# D1_Breakout_-_LCD_TH_Dupont.net
KiCad netlist of a schematic drawn in EAGLE
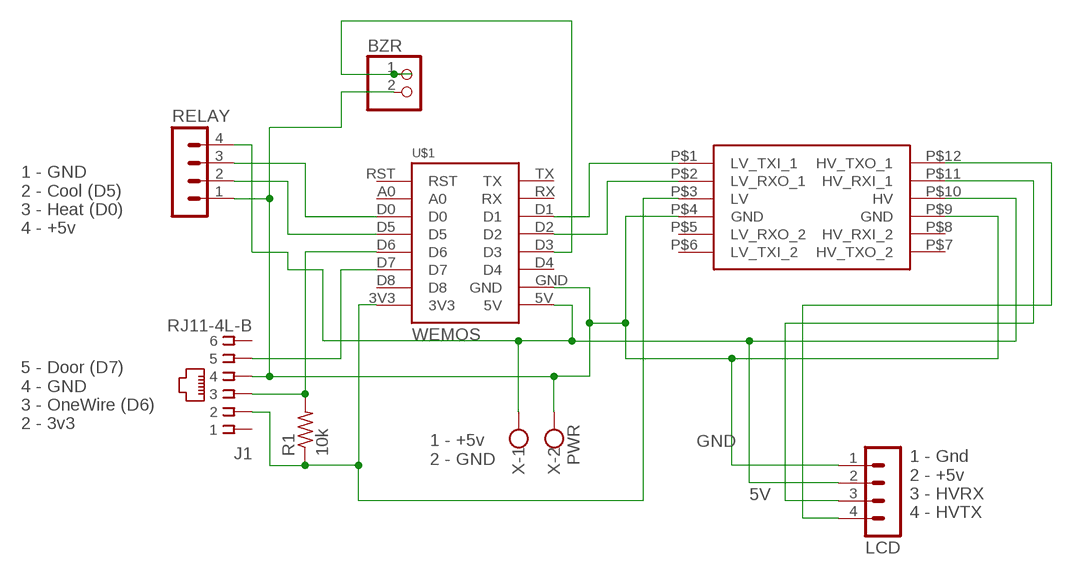
[diagram p0: schematic, sheet 1]

(export (version "E")
  (design (tool "Eeschema 10.0.6"))
  (components
    (comp (ref "BZR")
      (value "PINHD-1X2")
      (footprint "eagle-import:1X02")
      (libsource (lib "eagle-import") (part "PINHD-1X2"))
    )
    (comp (ref "J1")
      (value "RJ11-4L-B")
      (footprint "eagle-import:RJ11-NO_SHIELD")
      (fields (field (name "MF") "TYCO ELECTRONICS"))
      (libsource (lib "eagle-import") (part "RJ11-4L-B"))
    )
    (comp (ref "LCD")
      (value "MA04-1")
      (footprint "eagle-import:MA04-1")
      (libsource (lib "eagle-import") (part "MA04-1"))
    )
    (comp (ref "R1")
      (value "10k")
      (footprint "eagle-import:0207_5V")
      (libsource (lib "eagle-import") (part "R-US_0207/5V"))
    )
    (comp (ref "RELAY")
      (value "MA04-1")
      (footprint "eagle-import:MA04-1")
      (libsource (lib "eagle-import") (part "MA04-1"))
    )
    (comp (ref "U$1")
      (value "WEMOS")
      (footprint "eagle-import:WEMOS")
      (libsource (lib "eagle-import") (part "WEMOS"))
    )
    (comp (ref "U$3")
      (value "LOGIC_LEVEL_CONVERTER")
      (footprint "eagle-import:LOGIC_LEVEL_CONVERTER")
      (libsource (lib "eagle-import") (part "LOGIC_LEVEL_CONVERTER"))
    )
    (comp (ref "X")
      (value "PWR")
      (footprint "eagle-import:W237-102")
      (fields (field (name "MPN") "237-102"))
      (libsource (lib "eagle-import") (part "W237-102"))
    )
  )
  (nets
    (net (code "1") (name "/5V") (class "Default")
      (node (ref "LCD") (pin "2") (pinfunction "2_2") (pintype "passive"))
      (node (ref "RELAY") (pin "4") (pinfunction "4_4") (pintype "passive"))
      (node (ref "U$1") (pin "5V") (pinfunction "5V_5V") (pintype "bidirectional"))
      (node (ref "U$3") (pin "P$10") (pinfunction "HV_P$10") (pintype "bidirectional"))
      (node (ref "X") (pin "1") (pinfunction "KL_1") (pintype "passive"))
    )
    (net (code "2") (name "/GND") (class "Default")
      (node (ref "BZR") (pin "2") (pinfunction "2_2") (pintype "passive"))
      (node (ref "J1") (pin "4") (pinfunction "4_4") (pintype "passive"))
      (node (ref "LCD") (pin "1") (pinfunction "1_1") (pintype "passive"))
      (node (ref "RELAY") (pin "1") (pinfunction "1_1") (pintype "passive"))
      (node (ref "U$1") (pin "GND") (pinfunction "GND_GND") (pintype "bidirectional"))
      (node (ref "U$3") (pin "P$4") (pinfunction "GND_P$4") (pintype "bidirectional"))
      (node (ref "U$3") (pin "P$9") (pinfunction "GND_P$9") (pintype "bidirectional"))
      (node (ref "X") (pin "2") (pinfunction "KL_2") (pintype "passive"))
    )
    (net (code "3") (name "Net-(BZR-Pad1)") (class "Default")
      (node (ref "BZR") (pin "1") (pinfunction "1_1") (pintype "passive"))
      (node (ref "U$1") (pin "D3") (pinfunction "D3_D3") (pintype "bidirectional"))
    )
    (net (code "4") (name "Net-(J1-Pad3)") (class "Default")
      (node (ref "J1") (pin "3") (pinfunction "3_3") (pintype "passive"))
      (node (ref "R1") (pin "2") (pinfunction "2_2") (pintype "passive"))
      (node (ref "U$1") (pin "D6") (pinfunction "D6_D6") (pintype "bidirectional"))
    )
    (net (code "5") (name "Net-(J1-Pad5)") (class "Default")
      (node (ref "J1") (pin "5") (pinfunction "5_5") (pintype "passive"))
      (node (ref "U$1") (pin "D7") (pinfunction "D7_D7") (pintype "bidirectional"))
    )
    (net (code "6") (name "Net-(RELAY-Pad2)") (class "Default")
      (node (ref "RELAY") (pin "2") (pinfunction "2_2") (pintype "passive"))
      (node (ref "U$1") (pin "D5") (pinfunction "D5_D5") (pintype "bidirectional"))
    )
    (net (code "7") (name "Net-(RELAY-Pad3)") (class "Default")
      (node (ref "RELAY") (pin "3") (pinfunction "3_3") (pintype "passive"))
      (node (ref "U$1") (pin "D0") (pinfunction "D0_D0") (pintype "bidirectional"))
    )
    (net (code "8") (name "Net-(U$3-HV_RXI_1)") (class "Default")
      (node (ref "LCD") (pin "3") (pinfunction "3_3") (pintype "passive"))
      (node (ref "U$3") (pin "P$11") (pinfunction "HV_RXI_1_P$11") (pintype "bidirectional"))
    )
    (net (code "9") (name "Net-(U$3-HV_TXO_1)") (class "Default")
      (node (ref "LCD") (pin "4") (pinfunction "4_4") (pintype "passive"))
      (node (ref "U$3") (pin "P$12") (pinfunction "HV_TXO_1_P$12") (pintype "bidirectional"))
    )
    (net (code "10") (name "Net-(U$3-LV)") (class "Default")
      (node (ref "J1") (pin "2") (pinfunction "2_2") (pintype "passive"))
      (node (ref "R1") (pin "1") (pinfunction "1_1") (pintype "passive"))
      (node (ref "U$1") (pin "3V3") (pinfunction "3V3_3V3") (pintype "bidirectional"))
      (node (ref "U$3") (pin "P$3") (pinfunction "LV_P$3") (pintype "bidirectional"))
    )
    (net (code "11") (name "Net-(U$3-LV_RXO_1)") (class "Default")
      (node (ref "U$1") (pin "D2") (pinfunction "D2_D2") (pintype "bidirectional"))
      (node (ref "U$3") (pin "P$2") (pinfunction "LV_RXO_1_P$2") (pintype "bidirectional"))
    )
    (net (code "12") (name "Net-(U$3-LV_TXI_1)") (class "Default")
      (node (ref "U$1") (pin "D1") (pinfunction "D1_D1") (pintype "bidirectional"))
      (node (ref "U$3") (pin "P$1") (pinfunction "LV_TXI_1_P$1") (pintype "bidirectional"))
    )
    (net (code "13") (name "unconnected-(J1-Pad1)") (class "Default")
      (node (ref "J1") (pin "1") (pinfunction "1_1") (pintype "passive"))
    )
    (net (code "14") (name "unconnected-(J1-Pad6)") (class "Default")
      (node (ref "J1") (pin "6") (pinfunction "6_6") (pintype "passive"))
    )
    (net (code "15") (name "unconnected-(U$1-PadA0)") (class "Default")
      (node (ref "U$1") (pin "A0") (pinfunction "A0_A0") (pintype "bidirectional"))
    )
    (net (code "16") (name "unconnected-(U$1-PadD4)") (class "Default")
      (node (ref "U$1") (pin "D4") (pinfunction "D4_D4") (pintype "bidirectional"))
    )
    (net (code "17") (name "unconnected-(U$1-PadD8)") (class "Default")
      (node (ref "U$1") (pin "D8") (pinfunction "D8_D8") (pintype "bidirectional"))
    )
    (net (code "18") (name "unconnected-(U$1-PadRST)") (class "Default")
      (node (ref "U$1") (pin "RST") (pinfunction "RST_RST") (pintype "bidirectional"))
    )
    (net (code "19") (name "unconnected-(U$1-PadRX)") (class "Default")
      (node (ref "U$1") (pin "RX") (pinfunction "RX_RX") (pintype "bidirectional"))
    )
    (net (code "20") (name "unconnected-(U$1-PadTX)") (class "Default")
      (node (ref "U$1") (pin "TX") (pinfunction "TX_TX") (pintype "bidirectional"))
    )
    (net (code "21") (name "unconnected-(U$3-HV_RXI_2-PadP$8)") (class "Default")
      (node (ref "U$3") (pin "P$8") (pinfunction "HV_RXI_2_P$8") (pintype "bidirectional"))
    )
    (net (code "22") (name "unconnected-(U$3-HV_TXO_2-PadP$7)") (class "Default")
      (node (ref "U$3") (pin "P$7") (pinfunction "HV_TXO_2_P$7") (pintype "bidirectional"))
    )
    (net (code "23") (name "unconnected-(U$3-LV_RXO_2-PadP$5)") (class "Default")
      (node (ref "U$3") (pin "P$5") (pinfunction "LV_RXO_2_P$5") (pintype "bidirectional"))
    )
    (net (code "24") (name "unconnected-(U$3-LV_TXI_2-PadP$6)") (class "Default")
      (node (ref "U$3") (pin "P$6") (pinfunction "LV_TXI_2_P$6") (pintype "bidirectional"))
    )
  )
)
